# sparkfun-9dof-razor-imu.net
KiCad netlist of a schematic drawn in EAGLE
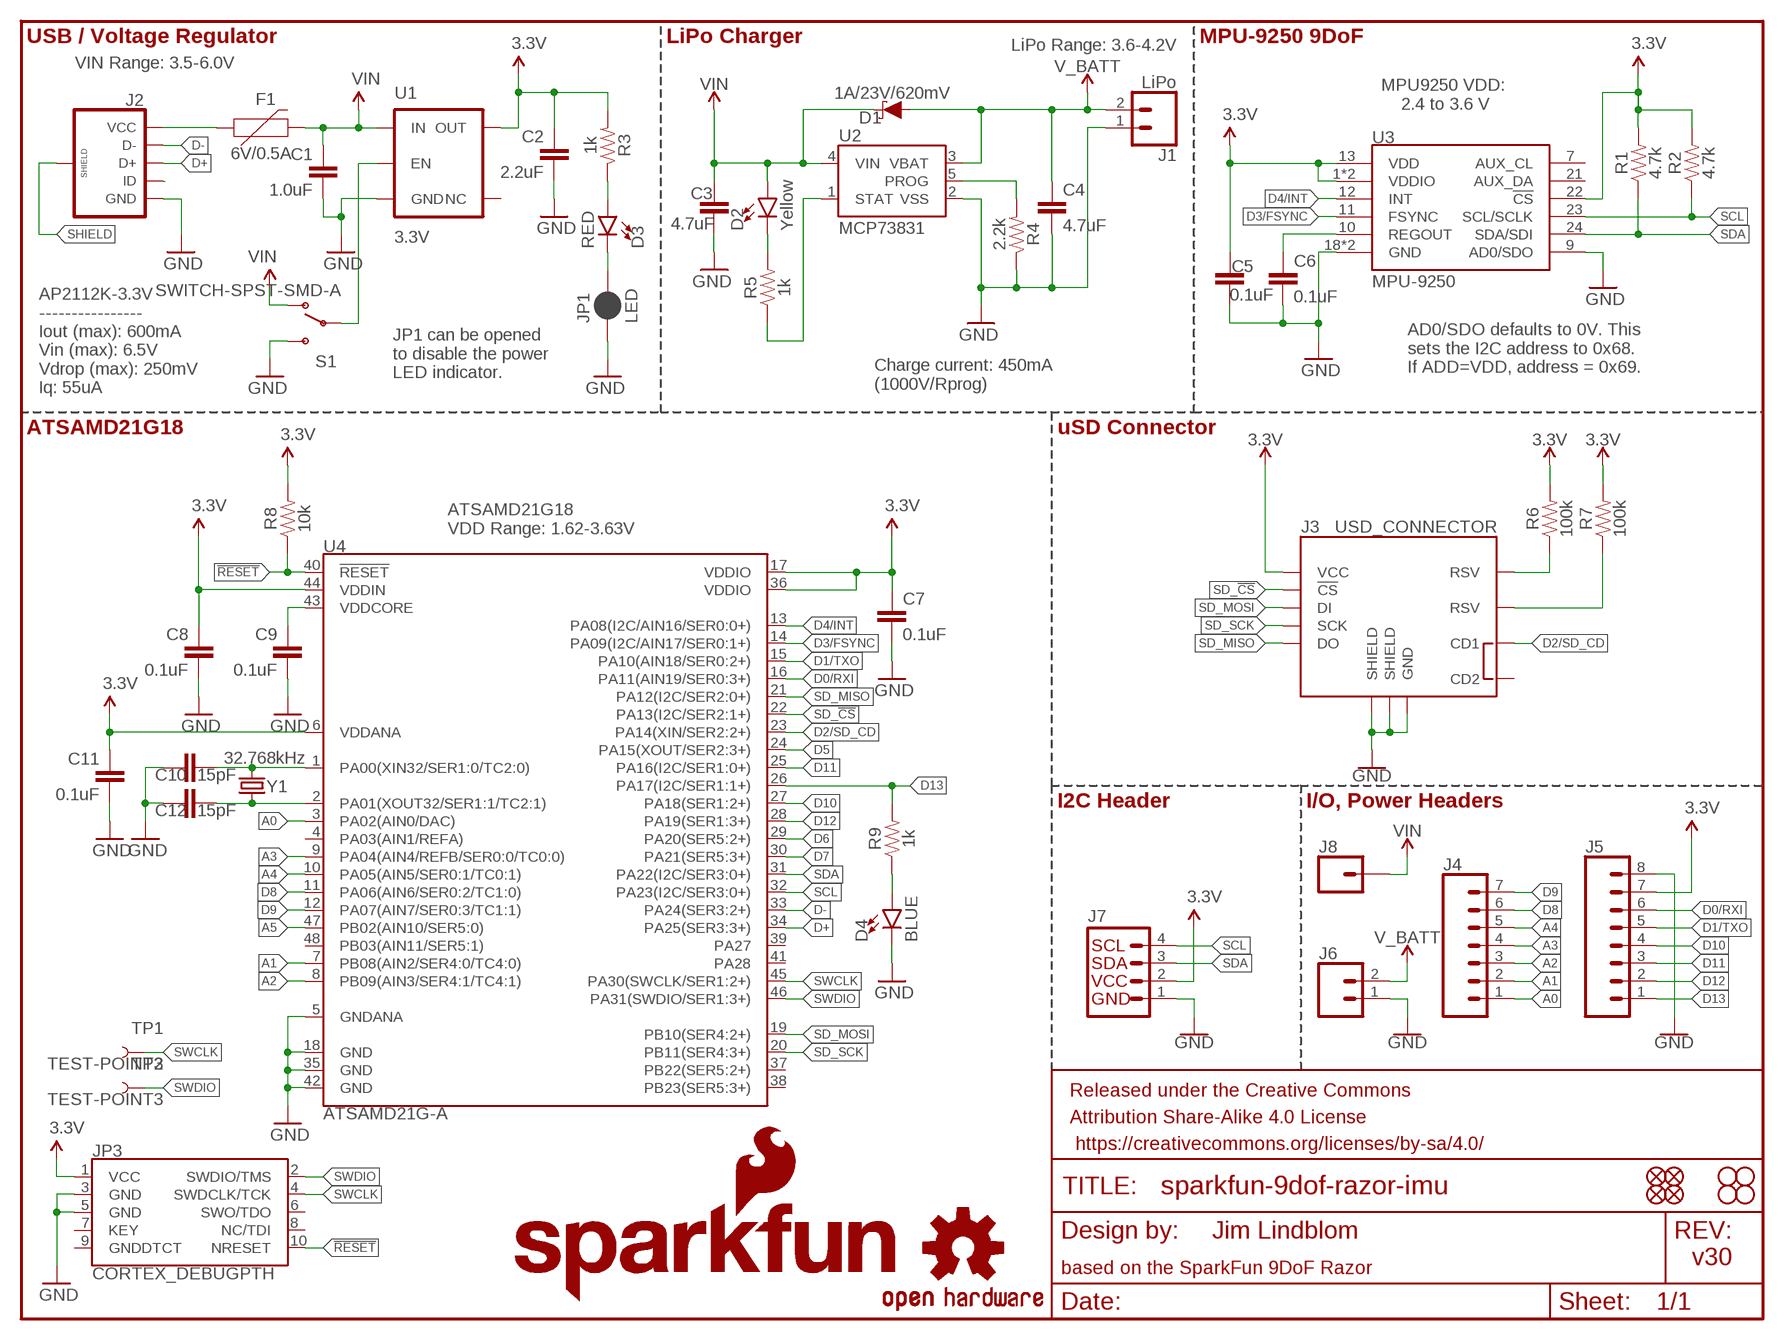
[diagram p0: schematic, sheet 1]

(export (version "E")
  (design (tool "Eeschema 10.0.6"))
  (components
    (comp (ref "C1")
      (value "1.0uF")
      (footprint "eagle-import:0603")
      (libsource (lib "eagle-import") (part "1.0UF-0603-16V-10%"))
    )
    (comp (ref "C2")
      (value "2.2uF")
      (footprint "eagle-import:0603")
      (libsource (lib "eagle-import") (part "2.2UF-0603-10V-20%"))
    )
    (comp (ref "C3")
      (value "4.7uF")
      (footprint "eagle-import:0603")
      (libsource (lib "eagle-import") (part "4.7UF0603"))
    )
    (comp (ref "C4")
      (value "4.7uF")
      (footprint "eagle-import:0603")
      (libsource (lib "eagle-import") (part "4.7UF0603"))
    )
    (comp (ref "C5")
      (value "0.1uF")
      (footprint "eagle-import:0603")
      (libsource (lib "eagle-import") (part "0.1UF-0603-25V-(+80/-20%)"))
    )
    (comp (ref "C6")
      (value "0.1uF")
      (footprint "eagle-import:0603")
      (libsource (lib "eagle-import") (part "0.1UF-0603-25V-(+80/-20%)"))
    )
    (comp (ref "C7")
      (value "0.1uF")
      (footprint "eagle-import:0603")
      (libsource (lib "eagle-import") (part "0.1UF-0603-25V-(+80/-20%)"))
    )
    (comp (ref "C8")
      (value "0.1uF")
      (footprint "eagle-import:0603")
      (libsource (lib "eagle-import") (part "0.1UF-0603-25V-(+80/-20%)"))
    )
    (comp (ref "C9")
      (value "0.1uF")
      (footprint "eagle-import:0603")
      (libsource (lib "eagle-import") (part "0.1UF-0603-25V-(+80/-20%)"))
    )
    (comp (ref "C10")
      (value "15pF")
      (footprint "eagle-import:0603")
      (libsource (lib "eagle-import") (part "15PF-0603-50V-5%"))
    )
    (comp (ref "C11")
      (value "0.1uF")
      (footprint "eagle-import:0603")
      (libsource (lib "eagle-import") (part "0.1UF-0603-100V-10%"))
    )
    (comp (ref "C12")
      (value "15pF")
      (footprint "eagle-import:0603")
      (libsource (lib "eagle-import") (part "15PF-0603-50V-5%"))
    )
    (comp (ref "D1")
      (value "1A/23V/620mV")
      (footprint "eagle-import:SOD-323")
      (libsource (lib "eagle-import") (part "DIODE-SCHOTTKY-BAT20J"))
    )
    (comp (ref "D2")
      (value "Yellow")
      (footprint "eagle-import:LED-0603")
      (libsource (lib "eagle-import") (part "LED-YELLOW0603"))
    )
    (comp (ref "D3")
      (value "RED")
      (footprint "eagle-import:LED-0603")
      (libsource (lib "eagle-import") (part "LED-RED0603"))
    )
    (comp (ref "D4")
      (value "BLUE")
      (footprint "eagle-import:LED-0603")
      (libsource (lib "eagle-import") (part "LED-BLUE0603"))
    )
    (comp (ref "F1")
      (value "6V/0.5A")
      (footprint "eagle-import:1206")
      (libsource (lib "eagle-import") (part "PPTC_HALF-AMP"))
    )
    (comp (ref "FD1")
      (value "FIDUCIAL1X2")
      (footprint "eagle-import:FIDUCIAL-1X2")
      (libsource (lib "eagle-import") (part "FIDUCIAL1X2"))
    )
    (comp (ref "FD2")
      (value "FIDUCIAL1X2")
      (footprint "eagle-import:FIDUCIAL-1X2")
      (libsource (lib "eagle-import") (part "FIDUCIAL1X2"))
    )
    (comp (ref "FD3")
      (value "FIDUCIAL1X2")
      (footprint "eagle-import:FIDUCIAL-1X2")
      (libsource (lib "eagle-import") (part "FIDUCIAL1X2"))
    )
    (comp (ref "FD4")
      (value "FIDUCIAL1X2")
      (footprint "eagle-import:FIDUCIAL-1X2")
      (libsource (lib "eagle-import") (part "FIDUCIAL1X2"))
    )
    (comp (ref "FRAME1")
      (value "FRAME-LETTER")
      (footprint "eagle-import:CREATIVE_COMMONS")
      (libsource (lib "eagle-import") (part "FRAME-LETTER"))
    )
    (comp (ref "H1")
      (value "STAND-OFF")
      (footprint "eagle-import:STAND-OFF")
      (libsource (lib "eagle-import") (part "STAND-OFF"))
    )
    (comp (ref "H2")
      (value "STAND-OFF")
      (footprint "eagle-import:STAND-OFF")
      (libsource (lib "eagle-import") (part "STAND-OFF"))
    )
    (comp (ref "H3")
      (value "STAND-OFF")
      (footprint "eagle-import:STAND-OFF")
      (libsource (lib "eagle-import") (part "STAND-OFF"))
    )
    (comp (ref "H4")
      (value "STAND-OFF")
      (footprint "eagle-import:STAND-OFF")
      (libsource (lib "eagle-import") (part "STAND-OFF"))
    )
    (comp (ref "J1")
      (value "LiPo")
      (footprint "eagle-import:JST-2-SMD")
      (libsource (lib "eagle-import") (part "CONN_02-JST-2MM-SMT"))
    )
    (comp (ref "J2")
      (value "USB_MICROB_PLUGCONN-11752")
      (footprint "eagle-import:USB-B-MICRO-SMD_V03")
      (libsource (lib "eagle-import") (part "USB_MICROB_PLUGCONN-11752"))
    )
    (comp (ref "J3")
      (value "USD_CONNECTOR")
      (footprint "eagle-import:MICRO-SD-SOCKET-PP")
      (libsource (lib "eagle-import") (part "USD_CONNECTOR"))
    )
    (comp (ref "J4")
      (value "CONN_07")
      (footprint "eagle-import:1X07")
      (libsource (lib "eagle-import") (part "CONN_07"))
    )
    (comp (ref "J5")
      (value "CONN_08\"")
      (footprint "eagle-import:1X08")
      (libsource (lib "eagle-import") (part "CONN_08{dblquote}"))
    )
    (comp (ref "J6")
      (value "CONN_02")
      (footprint "eagle-import:1X02")
      (libsource (lib "eagle-import") (part "CONN_02"))
    )
    (comp (ref "J7")
      (value "I2C_STANDARD")
      (footprint "eagle-import:1X04")
      (libsource (lib "eagle-import") (part "I2C_STANDARD"))
    )
    (comp (ref "J8")
      (value "CONN_01")
      (footprint "eagle-import:1X01")
      (libsource (lib "eagle-import") (part "CONN_01"))
    )
    (comp (ref "JP1")
      (value "LED")
      (footprint "eagle-import:SMT-JUMPER_2_NC_PASTE_NO-SILK")
      (libsource (lib "eagle-import") (part "JUMPER-SMT_2_NC_PASTE_NO-SILK"))
    )
    (comp (ref "JP3")
      (value "CORTEX_DEBUGPTH")
      (footprint "eagle-import:2X5-PTH-1.27MM")
      (libsource (lib "eagle-import") (part "CORTEX_DEBUGPTH"))
    )
    (comp (ref "LOGO1")
      (value "SFE_LOGO_FLAME.1_INCH")
      (footprint "eagle-import:SFE_LOGO_FLAME_.1")
      (libsource (lib "eagle-import") (part "SFE_LOGO_FLAME.1_INCH"))
    )
    (comp (ref "LOGO2")
      (value "OSHW-LOGOS")
      (footprint "eagle-import:OSHW-LOGO-S")
      (libsource (lib "eagle-import") (part "OSHW-LOGOS"))
    )
    (comp (ref "LOGO3")
      (value "SFE_LOGO_NAME.1_INCH")
      (footprint "eagle-import:SFE_LOGO_NAME_.1")
      (libsource (lib "eagle-import") (part "SFE_LOGO_NAME.1_INCH"))
    )
    (comp (ref "R1")
      (value "4.7k")
      (footprint "eagle-import:0603")
      (libsource (lib "eagle-import") (part "4.7KOHM-0603-1/10W-1%"))
    )
    (comp (ref "R2")
      (value "4.7k")
      (footprint "eagle-import:0603")
      (libsource (lib "eagle-import") (part "4.7KOHM-0603-1/10W-1%"))
    )
    (comp (ref "R3")
      (value "1k")
      (footprint "eagle-import:0603")
      (libsource (lib "eagle-import") (part "1KOHM-0603-1/10W-1%"))
    )
    (comp (ref "R4")
      (value "2.2k")
      (footprint "eagle-import:0603")
      (libsource (lib "eagle-import") (part "2.2KOHM-0603-1/10W-1%"))
    )
    (comp (ref "R5")
      (value "1k")
      (footprint "eagle-import:0603")
      (libsource (lib "eagle-import") (part "1KOHM-0603-1/10W-1%"))
    )
    (comp (ref "R6")
      (value "100k")
      (footprint "eagle-import:0603")
      (libsource (lib "eagle-import") (part "100KOHM-0603-1/10W-1%"))
    )
    (comp (ref "R7")
      (value "100k")
      (footprint "eagle-import:0603")
      (libsource (lib "eagle-import") (part "100KOHM-0603-1/10W-1%"))
    )
    (comp (ref "R8")
      (value "10k")
      (footprint "eagle-import:0603")
      (libsource (lib "eagle-import") (part "10KOHM-0603-1/10W-1%"))
    )
    (comp (ref "R9")
      (value "1k")
      (footprint "eagle-import:0603")
      (libsource (lib "eagle-import") (part "1KOHM-0603-1/10W-1%"))
    )
    (comp (ref "S1")
      (value "SWITCH-SPST-SMD-A")
      (footprint "eagle-import:SWITCH-SPST-SMD-A")
      (libsource (lib "eagle-import") (part "SWITCH-SPDT-SMD-A"))
    )
    (comp (ref "TP1")
      (value "TEST-POINT3")
      (footprint "eagle-import:PAD.03X.03")
      (libsource (lib "eagle-import") (part "TEST-POINT3"))
    )
    (comp (ref "TP2")
      (value "TEST-POINT3")
      (footprint "eagle-import:PAD.03X.03")
      (libsource (lib "eagle-import") (part "TEST-POINT3"))
    )
    (comp (ref "U1")
      (value "3.3V")
      (footprint "eagle-import:SOT23-5")
      (libsource (lib "eagle-import") (part "V_REG_AP2112K-3.3V"))
    )
    (comp (ref "U2")
      (value "MCP73831")
      (footprint "eagle-import:SOT23-5")
      (libsource (lib "eagle-import") (part "MCP73831"))
    )
    (comp (ref "U3")
      (value "MPU-9250")
      (footprint "eagle-import:QFN24-3X3")
      (libsource (lib "eagle-import") (part "MPU-9250"))
    )
    (comp (ref "U4")
      (value "ATSAMD21G-A")
      (footprint "eagle-import:TQFP-48")
      (libsource (lib "eagle-import") (part "ATSAMD21G-A"))
    )
    (comp (ref "Y1")
      (value "32.768kHz")
      (footprint "eagle-import:CRYSTAL-SMD-3.2X1.5MM")
      (libsource (lib "eagle-import") (part "CRYSTAL-32.768KHZSMD-3.2X1.5"))
    )
  )
  (nets
    (net (code "1") (name "/SD_~{CS}") (class "Default")
      (node (ref "J3") (pin "CS") (pinfunction "~{CS}_CS") (pintype "bidirectional"))
      (node (ref "U4") (pin "22") (pinfunction "PA13(I2C/SER2:1+)_22") (pintype "bidirectional"))
    )
    (net (code "2") (name "/~{RESET}") (class "Default")
      (node (ref "JP3") (pin "10") (pinfunction "NRESET_10") (pintype "bidirectional"))
      (node (ref "R8") (pin "1") (pinfunction "1_1") (pintype "passive"))
      (node (ref "U4") (pin "40") (pinfunction "~{RESET}_40") (pintype "bidirectional"))
    )
    (net (code "3") (name "3.3V") (class "Default")
      (node (ref "C11") (pin "1") (pinfunction "1_1") (pintype "passive"))
      (node (ref "C2") (pin "1") (pinfunction "1_1") (pintype "passive"))
      (node (ref "C5") (pin "1") (pinfunction "1_1") (pintype "passive"))
      (node (ref "C7") (pin "1") (pinfunction "1_1") (pintype "passive"))
      (node (ref "C8") (pin "1") (pinfunction "1_1") (pintype "passive"))
      (node (ref "J3") (pin "VCC") (pinfunction "VCC_VCC") (pintype "bidirectional"))
      (node (ref "J5") (pin "7") (pinfunction "7_7") (pintype "passive"))
      (node (ref "J7") (pin "2") (pinfunction "2_2") (pintype "passive"))
      (node (ref "JP3") (pin "1") (pinfunction "VCC_1") (pintype "bidirectional"))
      (node (ref "R1") (pin "2") (pinfunction "2_2") (pintype "passive"))
      (node (ref "R2") (pin "2") (pinfunction "2_2") (pintype "passive"))
      (node (ref "R3") (pin "2") (pinfunction "2_2") (pintype "passive"))
      (node (ref "R6") (pin "2") (pinfunction "2_2") (pintype "passive"))
      (node (ref "R7") (pin "2") (pinfunction "2_2") (pintype "passive"))
      (node (ref "R8") (pin "2") (pinfunction "2_2") (pintype "passive"))
      (node (ref "U1") (pin "5") (pinfunction "OUT_5") (pintype "passive"))
      (node (ref "U3") (pin "1") (pinfunction "VDDIO_1") (pintype "bidirectional"))
      (node (ref "U3") (pin "13") (pinfunction "VDD_13") (pintype "bidirectional"))
      (node (ref "U3") (pin "22") (pinfunction "~{CS}_22") (pintype "bidirectional"))
      (node (ref "U3") (pin "8") (pinfunction "VDDIO_8") (pintype "bidirectional"))
      (node (ref "U4") (pin "17") (pinfunction "VDDIO_17") (pintype "bidirectional"))
      (node (ref "U4") (pin "36") (pinfunction "VDDIO_36") (pintype "bidirectional"))
      (node (ref "U4") (pin "44") (pinfunction "VDDIN_44") (pintype "bidirectional"))
      (node (ref "U4") (pin "6") (pinfunction "VDDANA_6") (pintype "bidirectional"))
    )
    (net (code "4") (name "A0") (class "Default")
      (node (ref "J4") (pin "1") (pinfunction "1_1") (pintype "passive"))
      (node (ref "U4") (pin "3") (pinfunction "PA02(AIN0/DAC)_3") (pintype "bidirectional"))
    )
    (net (code "5") (name "A1") (class "Default")
      (node (ref "J4") (pin "2") (pinfunction "2_2") (pintype "passive"))
      (node (ref "U4") (pin "7") (pinfunction "PB08(AIN2/SER4:0/TC4:0)_7") (pintype "bidirectional"))
    )
    (net (code "6") (name "A2") (class "Default")
      (node (ref "J4") (pin "3") (pinfunction "3_3") (pintype "passive"))
      (node (ref "U4") (pin "8") (pinfunction "PB09(AIN3/SER4:1/TC4:1)_8") (pintype "bidirectional"))
    )
    (net (code "7") (name "A3") (class "Default")
      (node (ref "J4") (pin "4") (pinfunction "4_4") (pintype "passive"))
      (node (ref "U4") (pin "9") (pinfunction "PA04(AIN4/REFB/SER0:0/TC0:0)_9") (pintype "bidirectional"))
    )
    (net (code "8") (name "A4") (class "Default")
      (node (ref "J4") (pin "5") (pinfunction "5_5") (pintype "passive"))
      (node (ref "U4") (pin "10") (pinfunction "PA05(AIN5/SER0:1/TC0:1)_10") (pintype "bidirectional"))
    )
    (net (code "9") (name "A5") (class "Default")
      (node (ref "U4") (pin "47") (pinfunction "PB02(AIN10/SER5:0)_47") (pintype "bidirectional"))
    )
    (net (code "10") (name "D+") (class "Default")
      (node (ref "J2") (pin "D+") (pinfunction "D+_D+") (pintype "bidirectional"))
      (node (ref "U4") (pin "34") (pinfunction "PA25(SER3:3+)_34") (pintype "bidirectional"))
    )
    (net (code "11") (name "D-") (class "Default")
      (node (ref "J2") (pin "D-") (pinfunction "D-_D-") (pintype "bidirectional"))
      (node (ref "U4") (pin "33") (pinfunction "PA24(SER3:2+)_33") (pintype "bidirectional"))
    )
    (net (code "12") (name "D0{slash}RXI") (class "Default")
      (node (ref "J5") (pin "6") (pinfunction "6_6") (pintype "passive"))
      (node (ref "U4") (pin "16") (pinfunction "PA11(AIN19/SER0:3+)_16") (pintype "bidirectional"))
    )
    (net (code "13") (name "D1{slash}TXO") (class "Default")
      (node (ref "J5") (pin "5") (pinfunction "5_5") (pintype "passive"))
      (node (ref "U4") (pin "15") (pinfunction "PA10(AIN18/SER0:2+)_15") (pintype "bidirectional"))
    )
    (net (code "14") (name "D2{slash}SD_CD") (class "Default")
      (node (ref "J3") (pin "CD1") (pinfunction "CD1_CD1") (pintype "bidirectional"))
      (node (ref "U4") (pin "23") (pinfunction "PA14(XIN/SER2:2+)_23") (pintype "bidirectional"))
    )
    (net (code "15") (name "D3{slash}FSYNC") (class "Default")
      (node (ref "U3") (pin "11") (pinfunction "FSYNC_11") (pintype "bidirectional"))
      (node (ref "U4") (pin "14") (pinfunction "PA09(I2C/AIN17/SER0:1+)_14") (pintype "bidirectional"))
    )
    (net (code "16") (name "D4{slash}INT") (class "Default")
      (node (ref "U3") (pin "12") (pinfunction "INT_12") (pintype "bidirectional"))
      (node (ref "U4") (pin "13") (pinfunction "PA08(I2C/AIN16/SER0:0+)_13") (pintype "bidirectional"))
    )
    (net (code "17") (name "D5") (class "Default")
      (node (ref "U4") (pin "24") (pinfunction "PA15(XOUT/SER2:3+)_24") (pintype "bidirectional"))
    )
    (net (code "18") (name "D6") (class "Default")
      (node (ref "U4") (pin "29") (pinfunction "PA20(SER5:2+)_29") (pintype "bidirectional"))
    )
    (net (code "19") (name "D7") (class "Default")
      (node (ref "U4") (pin "30") (pinfunction "PA21(SER5:3+)_30") (pintype "bidirectional"))
    )
    (net (code "20") (name "D8") (class "Default")
      (node (ref "J4") (pin "6") (pinfunction "6_6") (pintype "passive"))
      (node (ref "U4") (pin "11") (pinfunction "PA06(AIN6/SER0:2/TC1:0)_11") (pintype "bidirectional"))
    )
    (net (code "21") (name "D9") (class "Default")
      (node (ref "J4") (pin "7") (pinfunction "7_7") (pintype "passive"))
      (node (ref "U4") (pin "12") (pinfunction "PA07(AIN7/SER0:3/TC1:1)_12") (pintype "bidirectional"))
    )
    (net (code "22") (name "D10") (class "Default")
      (node (ref "J5") (pin "4") (pinfunction "4_4") (pintype "passive"))
      (node (ref "U4") (pin "27") (pinfunction "PA18(SER1:2+)_27") (pintype "bidirectional"))
    )
    (net (code "23") (name "D11") (class "Default")
      (node (ref "J5") (pin "3") (pinfunction "3_3") (pintype "passive"))
      (node (ref "U4") (pin "25") (pinfunction "PA16(I2C/SER1:0+)_25") (pintype "bidirectional"))
    )
    (net (code "24") (name "D12") (class "Default")
      (node (ref "J5") (pin "2") (pinfunction "2_2") (pintype "passive"))
      (node (ref "U4") (pin "28") (pinfunction "PA19(SER1:3+)_28") (pintype "bidirectional"))
    )
    (net (code "25") (name "D13") (class "Default")
      (node (ref "J5") (pin "1") (pinfunction "1_1") (pintype "passive"))
      (node (ref "R9") (pin "2") (pinfunction "2_2") (pintype "passive"))
      (node (ref "U4") (pin "26") (pinfunction "PA17(I2C/SER1:1+)_26") (pintype "bidirectional"))
    )
    (net (code "26") (name "GND") (class "Default")
      (node (ref "C1") (pin "2") (pinfunction "2_2") (pintype "passive"))
      (node (ref "C10") (pin "1") (pinfunction "1_1") (pintype "passive"))
      (node (ref "C11") (pin "2") (pinfunction "2_2") (pintype "passive"))
      (node (ref "C12") (pin "2") (pinfunction "2_2") (pintype "passive"))
      (node (ref "C2") (pin "2") (pinfunction "2_2") (pintype "passive"))
      (node (ref "C3") (pin "2") (pinfunction "2_2") (pintype "passive"))
      (node (ref "C4") (pin "2") (pinfunction "2_2") (pintype "passive"))
      (node (ref "C5") (pin "2") (pinfunction "2_2") (pintype "passive"))
      (node (ref "C6") (pin "2") (pinfunction "2_2") (pintype "passive"))
      (node (ref "C7") (pin "2") (pinfunction "2_2") (pintype "passive"))
      (node (ref "C8") (pin "2") (pinfunction "2_2") (pintype "passive"))
      (node (ref "C9") (pin "2") (pinfunction "2_2") (pintype "passive"))
      (node (ref "D4") (pin "C") (pinfunction "C_C") (pintype "passive"))
      (node (ref "J1") (pin "1") (pinfunction "2_1") (pintype "passive"))
      (node (ref "J2") (pin "GND") (pinfunction "GND_GND") (pintype "bidirectional"))
      (node (ref "J3") (pin "GND") (pinfunction "GND_GND") (pintype "bidirectional"))
      (node (ref "J3") (pin "GND1") (pinfunction "SHIELD_GND1") (pintype "bidirectional"))
      (node (ref "J3") (pin "GND3") (pinfunction "SHIELD_GND3") (pintype "bidirectional"))
      (node (ref "J5") (pin "8") (pinfunction "8_8") (pintype "passive"))
      (node (ref "J6") (pin "1") (pinfunction "1_1") (pintype "passive"))
      (node (ref "J7") (pin "1") (pinfunction "1_1") (pintype "passive"))
      (node (ref "JP1") (pin "1") (pinfunction "1_1") (pintype "passive"))
      (node (ref "JP3") (pin "3") (pinfunction "GND_3") (pintype "bidirectional"))
      (node (ref "JP3") (pin "5") (pinfunction "GND_5") (pintype "bidirectional"))
      (node (ref "R4") (pin "1") (pinfunction "1_1") (pintype "passive"))
      (node (ref "S1") (pin "3") (pinfunction "S_3") (pintype "passive"))
      (node (ref "U1") (pin "2") (pinfunction "GND_2") (pintype "input"))
      (node (ref "U2") (pin "2") (pinfunction "VSS_2") (pintype "power_in"))
      (node (ref "U3") (pin "18") (pinfunction "GND_18") (pintype "bidirectional"))
      (node (ref "U3") (pin "20") (pinfunction "GND_20") (pintype "bidirectional"))
      (node (ref "U3") (pin "9") (pinfunction "AD0/SDO_9") (pintype "bidirectional"))
      (node (ref "U4") (pin "18") (pinfunction "GND_18") (pintype "bidirectional"))
      (node (ref "U4") (pin "35") (pinfunction "GND_35") (pintype "bidirectional"))
      (node (ref "U4") (pin "42") (pinfunction "GND_42") (pintype "bidirectional"))
      (node (ref "U4") (pin "5") (pinfunction "GNDANA_5") (pintype "bidirectional"))
    )
    (net (code "27") (name "Net-(D2-PadC)") (class "Default")
      (node (ref "D2") (pin "C") (pinfunction "C_C") (pintype "passive"))
      (node (ref "R5") (pin "2") (pinfunction "2_2") (pintype "passive"))
    )
    (net (code "28") (name "Net-(D3-PadA)") (class "Default")
      (node (ref "D3") (pin "A") (pinfunction "A_A") (pintype "passive"))
      (node (ref "R3") (pin "1") (pinfunction "1_1") (pintype "passive"))
    )
    (net (code "29") (name "Net-(D3-PadC)") (class "Default")
      (node (ref "D3") (pin "C") (pinfunction "C_C") (pintype "passive"))
      (node (ref "JP1") (pin "2") (pinfunction "2_2") (pintype "passive"))
    )
    (net (code "30") (name "Net-(D4-PadA)") (class "Default")
      (node (ref "D4") (pin "A") (pinfunction "A_A") (pintype "passive"))
      (node (ref "R9") (pin "1") (pinfunction "1_1") (pintype "passive"))
    )
    (net (code "31") (name "Net-(J2-VCC)") (class "Default")
      (node (ref "F1") (pin "1") (pinfunction "1_1") (pintype "bidirectional"))
      (node (ref "J2") (pin "VBUS") (pinfunction "VCC_VBUS") (pintype "bidirectional"))
    )
    (net (code "32") (name "Net-(J3-RSV-PadRSV1)") (class "Default")
      (node (ref "J3") (pin "RSV1") (pinfunction "RSV_RSV1") (pintype "bidirectional"))
      (node (ref "R6") (pin "1") (pinfunction "1_1") (pintype "passive"))
    )
    (net (code "33") (name "Net-(J3-RSV-PadRSV2)") (class "Default")
      (node (ref "J3") (pin "RSV2") (pinfunction "RSV_RSV2") (pintype "bidirectional"))
      (node (ref "R7") (pin "1") (pinfunction "1_1") (pintype "passive"))
    )
    (net (code "34") (name "Net-(S1-P)") (class "Default")
      (node (ref "S1") (pin "2") (pinfunction "P_2") (pintype "passive"))
      (node (ref "U1") (pin "3") (pinfunction "EN_3") (pintype "input"))
    )
    (net (code "35") (name "Net-(U2-PROG)") (class "Default")
      (node (ref "R4") (pin "2") (pinfunction "2_2") (pintype "passive"))
      (node (ref "U2") (pin "5") (pinfunction "PROG_5") (pintype "input"))
    )
    (net (code "36") (name "Net-(U2-STAT)") (class "Default")
      (node (ref "R5") (pin "1") (pinfunction "1_1") (pintype "passive"))
      (node (ref "U2") (pin "1") (pinfunction "STAT_1") (pintype "output"))
    )
    (net (code "37") (name "Net-(U3-REGOUT)") (class "Default")
      (node (ref "C6") (pin "1") (pinfunction "1_1") (pintype "passive"))
      (node (ref "U3") (pin "10") (pinfunction "REGOUT_10") (pintype "bidirectional"))
    )
    (net (code "38") (name "Net-(U4-PA00(XIN32{slash}SER1:0{slash}TC2:0))") (class "Default")
      (node (ref "C10") (pin "2") (pinfunction "2_2") (pintype "passive"))
      (node (ref "U4") (pin "1") (pinfunction "PA00(XIN32/SER1:0/TC2:0)_1") (pintype "bidirectional"))
      (node (ref "Y1") (pin "P$2") (pinfunction "2_P$2") (pintype "passive"))
    )
    (net (code "39") (name "Net-(U4-PA01(XOUT32{slash}SER1:1{slash}TC2:1))") (class "Default")
      (node (ref "C12") (pin "1") (pinfunction "1_1") (pintype "passive"))
      (node (ref "U4") (pin "2") (pinfunction "PA01(XOUT32/SER1:1/TC2:1)_2") (pintype "bidirectional"))
      (node (ref "Y1") (pin "P$1") (pinfunction "1_P$1") (pintype "passive"))
    )
    (net (code "40") (name "Net-(U4-VDDCORE)") (class "Default")
      (node (ref "C9") (pin "1") (pinfunction "1_1") (pintype "passive"))
      (node (ref "U4") (pin "43") (pinfunction "VDDCORE_43") (pintype "bidirectional"))
    )
    (net (code "41") (name "SCL") (class "Default")
      (node (ref "J7") (pin "4") (pinfunction "4_4") (pintype "passive"))
      (node (ref "R2") (pin "1") (pinfunction "1_1") (pintype "passive"))
      (node (ref "U3") (pin "23") (pinfunction "SCL/SCLK_23") (pintype "bidirectional"))
      (node (ref "U4") (pin "32") (pinfunction "PA23(I2C/SER3:0+)_32") (pintype "bidirectional"))
    )
    (net (code "42") (name "SDA") (class "Default")
      (node (ref "J7") (pin "3") (pinfunction "3_3") (pintype "passive"))
      (node (ref "R1") (pin "1") (pinfunction "1_1") (pintype "passive"))
      (node (ref "U3") (pin "24") (pinfunction "SDA/SDI_24") (pintype "bidirectional"))
      (node (ref "U4") (pin "31") (pinfunction "PA22(I2C/SER3:0+)_31") (pintype "bidirectional"))
    )
    (net (code "43") (name "SD_MISO") (class "Default")
      (node (ref "J3") (pin "DO") (pinfunction "DO_DO") (pintype "bidirectional"))
      (node (ref "U4") (pin "21") (pinfunction "PA12(I2C/SER2:0+)_21") (pintype "bidirectional"))
    )
    (net (code "44") (name "SD_MOSI") (class "Default")
      (node (ref "J3") (pin "DI") (pinfunction "DI_DI") (pintype "bidirectional"))
      (node (ref "U4") (pin "19") (pinfunction "PB10(SER4:2+)_19") (pintype "bidirectional"))
    )
    (net (code "45") (name "SD_SCK") (class "Default")
      (node (ref "J3") (pin "SCLK") (pinfunction "SCK_SCLK") (pintype "bidirectional"))
      (node (ref "U4") (pin "20") (pinfunction "PB11(SER4:3+)_20") (pintype "bidirectional"))
    )
    (net (code "46") (name "SHIELD") (class "Default")
      (node (ref "J2") (pin "SHIELD1") (pinfunction "SHIELD_SHIELD1") (pintype "bidirectional"))
      (node (ref "J2") (pin "SHIELD2") (pinfunction "SHIELD_SHIELD2") (pintype "bidirectional"))
      (node (ref "J2") (pin "SHIELD3") (pinfunction "SHIELD_SHIELD3") (pintype "bidirectional"))
    )
    (net (code "47") (name "SWCLK") (class "Default")
      (node (ref "JP3") (pin "4") (pinfunction "SWDCLK/TCK_4") (pintype "bidirectional"))
      (node (ref "TP1") (pin "P$1") (pinfunction "1_P$1") (pintype "bidirectional"))
      (node (ref "U4") (pin "45") (pinfunction "PA30(SWCLK/SER1:2+)_45") (pintype "bidirectional"))
    )
    (net (code "48") (name "SWDIO") (class "Default")
      (node (ref "JP3") (pin "2") (pinfunction "SWDIO/TMS_2") (pintype "bidirectional"))
      (node (ref "TP2") (pin "P$1") (pinfunction "1_P$1") (pintype "bidirectional"))
      (node (ref "U4") (pin "46") (pinfunction "PA31(SWDIO/SER1:3+)_46") (pintype "bidirectional"))
    )
    (net (code "49") (name "VIN") (class "Default")
      (node (ref "C1") (pin "1") (pinfunction "1_1") (pintype "passive"))
      (node (ref "C3") (pin "1") (pinfunction "1_1") (pintype "passive"))
      (node (ref "D1") (pin "C") (pinfunction "C_C") (pintype "passive"))
      (node (ref "D2") (pin "A") (pinfunction "A_A") (pintype "passive"))
      (node (ref "F1") (pin "2") (pinfunction "2_2") (pintype "bidirectional"))
      (node (ref "J8") (pin "1") (pinfunction "1_1") (pintype "passive"))
      (node (ref "S1") (pin "1") (pinfunction "O_1") (pintype "passive"))
      (node (ref "U1") (pin "1") (pinfunction "IN_1") (pintype "input"))
      (node (ref "U2") (pin "4") (pinfunction "VIN_4") (pintype "power_in"))
    )
    (net (code "50") (name "V_BATT") (class "Default")
      (node (ref "C4") (pin "1") (pinfunction "1_1") (pintype "passive"))
      (node (ref "D1") (pin "A") (pinfunction "A_A") (pintype "passive"))
      (node (ref "J1") (pin "2") (pinfunction "1_2") (pintype "passive"))
      (node (ref "J6") (pin "2") (pinfunction "2_2") (pintype "passive"))
      (node (ref "U2") (pin "3") (pinfunction "VBAT_3") (pintype "power_in"))
    )
    (net (code "51") (name "unconnected-(J2-PadID)") (class "Default")
      (node (ref "J2") (pin "ID") (pinfunction "ID_ID") (pintype "bidirectional"))
    )
    (net (code "52") (name "unconnected-(J3-PadCD2)") (class "Default")
      (node (ref "J3") (pin "CD2") (pinfunction "CD2_CD2") (pintype "bidirectional"))
    )
    (net (code "53") (name "unconnected-(JP3-GNDDTCT-Pad9)") (class "Default")
      (node (ref "JP3") (pin "9") (pinfunction "GNDDTCT_9") (pintype "bidirectional"))
    )
    (net (code "54") (name "unconnected-(JP3-KEY-Pad7)") (class "Default")
      (node (ref "JP3") (pin "7") (pinfunction "KEY_7") (pintype "bidirectional"))
    )
    (net (code "55") (name "unconnected-(JP3-NC{slash}TDI-Pad8)") (class "Default")
      (node (ref "JP3") (pin "8") (pinfunction "NC/TDI_8") (pintype "bidirectional"))
    )
    (net (code "56") (name "unconnected-(JP3-SWO{slash}TDO-Pad6)") (class "Default")
      (node (ref "JP3") (pin "6") (pinfunction "SWO/TDO_6") (pintype "bidirectional"))
    )
    (net (code "57") (name "unconnected-(U1-NC-Pad4)") (class "Default")
      (node (ref "U1") (pin "4") (pinfunction "NC_4") (pintype "input"))
    )
    (net (code "58") (name "unconnected-(U3-AUX_CL-Pad7)") (class "Default")
      (node (ref "U3") (pin "7") (pinfunction "AUX_CL_7") (pintype "bidirectional"))
    )
    (net (code "59") (name "unconnected-(U3-AUX_DA-Pad21)") (class "Default")
      (node (ref "U3") (pin "21") (pinfunction "AUX_DA_21") (pintype "bidirectional"))
    )
    (net (code "60") (name "unconnected-(U4-PA03(AIN1{slash}REFA)-Pad4)") (class "Default")
      (node (ref "U4") (pin "4") (pinfunction "PA03(AIN1/REFA)_4") (pintype "bidirectional"))
    )
    (net (code "61") (name "unconnected-(U4-PA27-Pad39)") (class "Default")
      (node (ref "U4") (pin "39") (pinfunction "PA27_39") (pintype "bidirectional"))
    )
    (net (code "62") (name "unconnected-(U4-PA28-Pad41)") (class "Default")
      (node (ref "U4") (pin "41") (pinfunction "PA28_41") (pintype "bidirectional"))
    )
    (net (code "63") (name "unconnected-(U4-PB03(AIN11{slash}SER5:1)-Pad48)") (class "Default")
      (node (ref "U4") (pin "48") (pinfunction "PB03(AIN11/SER5:1)_48") (pintype "bidirectional"))
    )
    (net (code "64") (name "unconnected-(U4-PB22(SER5:2+)-Pad37)") (class "Default")
      (node (ref "U4") (pin "37") (pinfunction "PB22(SER5:2+)_37") (pintype "bidirectional"))
    )
    (net (code "65") (name "unconnected-(U4-PB23(SER5:3+)-Pad38)") (class "Default")
      (node (ref "U4") (pin "38") (pinfunction "PB23(SER5:3+)_38") (pintype "bidirectional"))
    )
  )
)
